# interface.net
KiCad netlist of a schematic drawn in Altium Designer
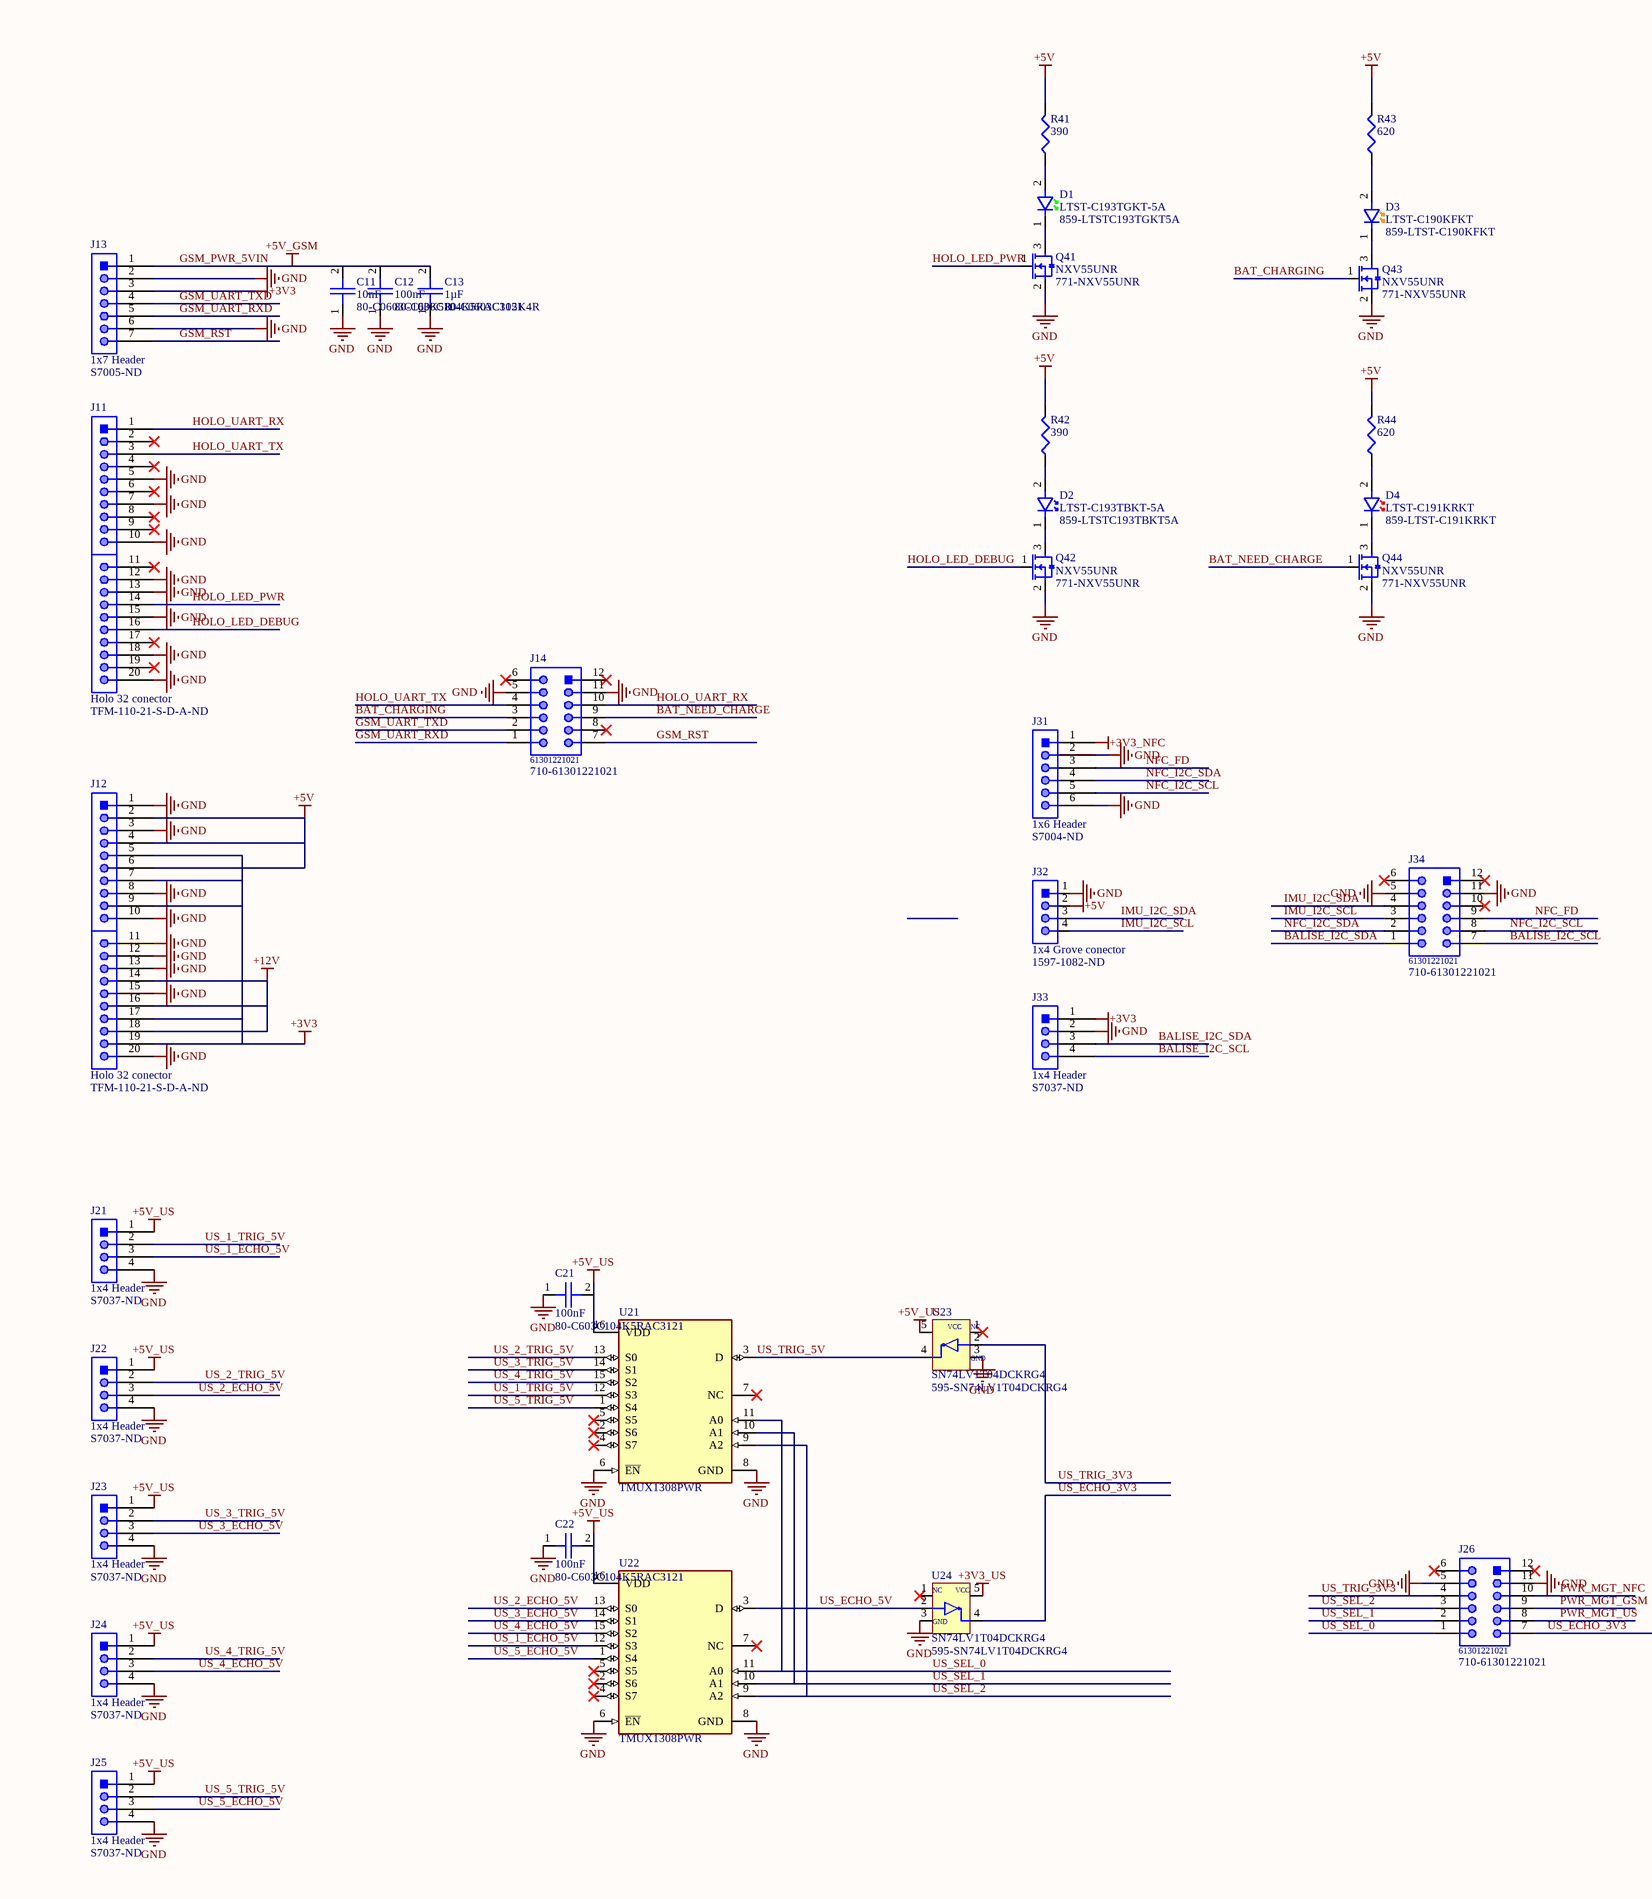
[diagram p0: interface.SchDoc, left]
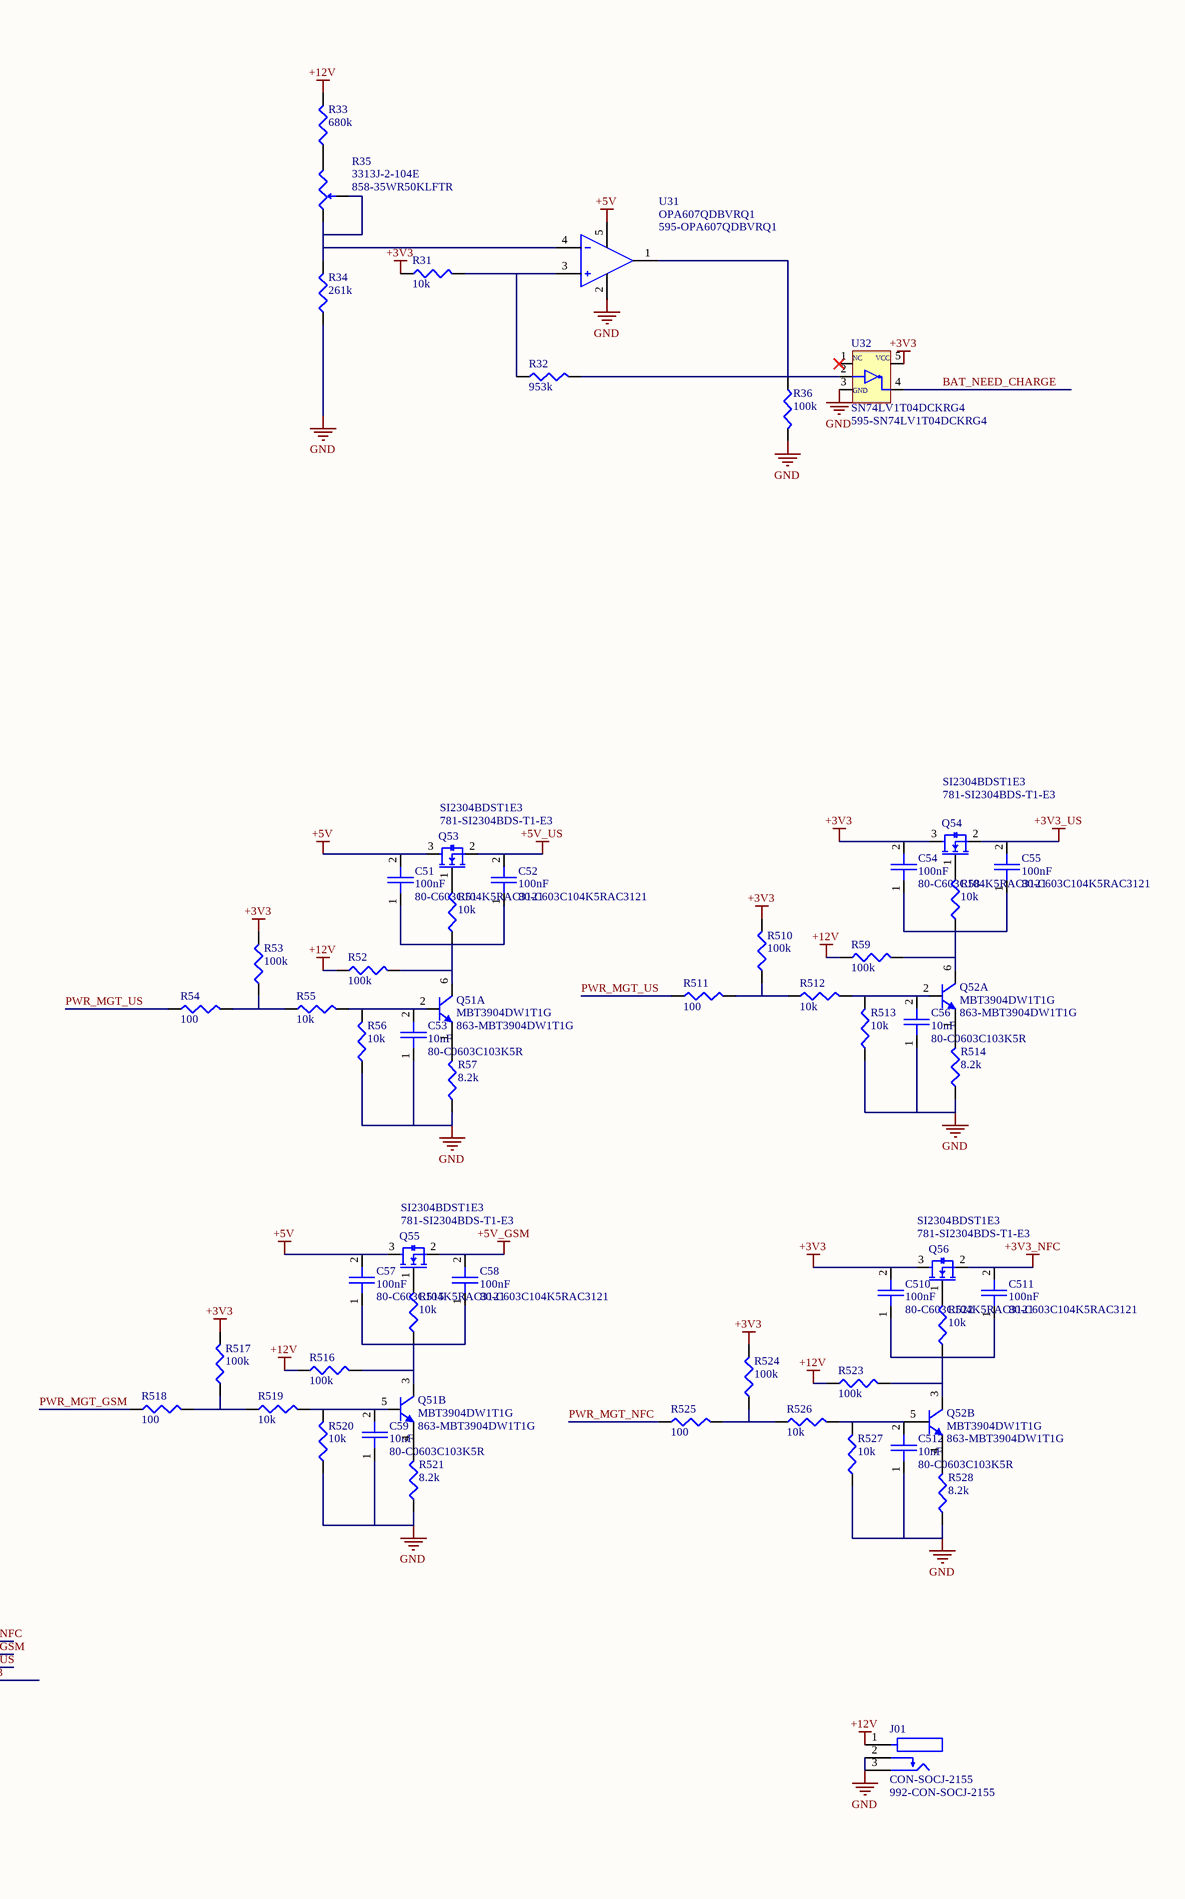
[diagram p1: interface.SchDoc, right]

(export (version "E")
  (design (tool "Eeschema 10.0.6"))
  (components
    (comp (ref "C11")
      (value "10nF")
      (footprint "FP-C0603C-CF-IPC_A")
      (description "CAP CER 10000PF 50V X7R 0603")
      (fields
        (field (name "MANUFACTURER") "KEMET")
        (field (name "MANUFACTURER PART NUMBER") "C0603C103K5RACTU")
        (field (name "SUPPLIER PART NUMBER 1") "80-C0603C103K5R")
      )
      (libsource (lib "interface_Schlib") (part "C0603C103K5RACTU"))
    )
    (comp (ref "C12")
      (value "100nF")
      (footprint "FP-C0603C104K5RAC3121-IPC_A")
      (description "Cap Ceramic 0.1uF 50V X7R 10% Pad SMD 0603 125°C T/R")
      (fields
        (field (name "MANUFACTURER") "KEMET")
        (field (name "MANUFACTURER PART NUMBER") "C0603C104K5RAC3121")
        (field (name "SUPPLIER PART NUMBER 1") "80-C603C104K5RAC3121")
      )
      (libsource (lib "interface_Schlib") (part "C0603C104K5RAC3121"))
    )
    (comp (ref "C13")
      (value "1µF")
      (footprint "CAPC1608X90X35NL15T15")
      (description "Cap Ceramic 1uF 16V X7R 10% SMD 0603 125°C Paper T/R")
      (fields
        (field (name "MANUFACTURER") "KEMET")
        (field (name "MANUFACTURER PART NUMBER") "C0603C105K4RACTU")
        (field (name "SUPPLIER PART NUMBER 1") "80-C0603C105K4R")
      )
      (libsource (lib "interface_Schlib") (part "C0603C105K4RACTU"))
    )
    (comp (ref "C21")
      (value "100nF")
      (footprint "FP-C0603C104K5RAC3121-IPC_A")
      (description "Cap Ceramic 0.1uF 50V X7R 10% Pad SMD 0603 125°C T/R")
      (fields
        (field (name "MANUFACTURER") "KEMET")
        (field (name "MANUFACTURER PART NUMBER") "C0603C104K5RAC3121")
        (field (name "SUPPLIER PART NUMBER 1") "80-C603C104K5RAC3121")
      )
      (libsource (lib "interface_Schlib") (part "C0603C104K5RAC3121"))
    )
    (comp (ref "C22")
      (value "100nF")
      (footprint "FP-C0603C104K5RAC3121-IPC_A")
      (description "Cap Ceramic 0.1uF 50V X7R 10% Pad SMD 0603 125°C T/R")
      (fields
        (field (name "MANUFACTURER") "KEMET")
        (field (name "MANUFACTURER PART NUMBER") "C0603C104K5RAC3121")
        (field (name "SUPPLIER PART NUMBER 1") "80-C603C104K5RAC3121")
      )
      (libsource (lib "interface_Schlib") (part "C0603C104K5RAC3121"))
    )
    (comp (ref "C51")
      (value "100nF")
      (footprint "FP-C0603C104K5RAC3121-IPC_A")
      (description "Cap Ceramic 0.1uF 50V X7R 10% Pad SMD 0603 125°C T/R")
      (fields
        (field (name "MANUFACTURER") "KEMET")
        (field (name "MANUFACTURER PART NUMBER") "C0603C104K5RAC3121")
        (field (name "SUPPLIER PART NUMBER 1") "80-C603C104K5RAC3121")
      )
      (libsource (lib "interface_Schlib") (part "C0603C104K5RAC3121"))
    )
    (comp (ref "C52")
      (value "100nF")
      (footprint "FP-C0603C104K5RAC3121-IPC_A")
      (description "Cap Ceramic 0.1uF 50V X7R 10% Pad SMD 0603 125°C T/R")
      (fields
        (field (name "MANUFACTURER") "KEMET")
        (field (name "MANUFACTURER PART NUMBER") "C0603C104K5RAC3121")
        (field (name "SUPPLIER PART NUMBER 1") "80-C603C104K5RAC3121")
      )
      (libsource (lib "interface_Schlib") (part "C0603C104K5RAC3121"))
    )
    (comp (ref "C53")
      (value "10nF")
      (footprint "FP-C0603C-CF-IPC_A")
      (description "CAP CER 10000PF 50V X7R 0603")
      (fields
        (field (name "MANUFACTURER") "KEMET")
        (field (name "MANUFACTURER PART NUMBER") "C0603C103K5RACTU")
        (field (name "SUPPLIER PART NUMBER 1") "80-C0603C103K5R")
      )
      (libsource (lib "interface_Schlib") (part "C0603C103K5RACTU"))
    )
    (comp (ref "C54")
      (value "100nF")
      (footprint "FP-C0603C104K5RAC3121-IPC_A")
      (description "Cap Ceramic 0.1uF 50V X7R 10% Pad SMD 0603 125°C T/R")
      (fields
        (field (name "MANUFACTURER") "KEMET")
        (field (name "MANUFACTURER PART NUMBER") "C0603C104K5RAC3121")
        (field (name "SUPPLIER PART NUMBER 1") "80-C603C104K5RAC3121")
      )
      (libsource (lib "interface_Schlib") (part "C0603C104K5RAC3121"))
    )
    (comp (ref "C55")
      (value "100nF")
      (footprint "FP-C0603C104K5RAC3121-IPC_A")
      (description "Cap Ceramic 0.1uF 50V X7R 10% Pad SMD 0603 125°C T/R")
      (fields
        (field (name "MANUFACTURER") "KEMET")
        (field (name "MANUFACTURER PART NUMBER") "C0603C104K5RAC3121")
        (field (name "SUPPLIER PART NUMBER 1") "80-C603C104K5RAC3121")
      )
      (libsource (lib "interface_Schlib") (part "C0603C104K5RAC3121"))
    )
    (comp (ref "C56")
      (value "10nF")
      (footprint "FP-C0603C-CF-IPC_A")
      (description "CAP CER 10000PF 50V X7R 0603")
      (fields
        (field (name "MANUFACTURER") "KEMET")
        (field (name "MANUFACTURER PART NUMBER") "C0603C103K5RACTU")
        (field (name "SUPPLIER PART NUMBER 1") "80-C0603C103K5R")
      )
      (libsource (lib "interface_Schlib") (part "C0603C103K5RACTU"))
    )
    (comp (ref "C57")
      (value "100nF")
      (footprint "FP-C0603C104K5RAC3121-IPC_A")
      (description "Cap Ceramic 0.1uF 50V X7R 10% Pad SMD 0603 125°C T/R")
      (fields
        (field (name "MANUFACTURER") "KEMET")
        (field (name "MANUFACTURER PART NUMBER") "C0603C104K5RAC3121")
        (field (name "SUPPLIER PART NUMBER 1") "80-C603C104K5RAC3121")
      )
      (libsource (lib "interface_Schlib") (part "C0603C104K5RAC3121"))
    )
    (comp (ref "C58")
      (value "100nF")
      (footprint "FP-C0603C104K5RAC3121-IPC_A")
      (description "Cap Ceramic 0.1uF 50V X7R 10% Pad SMD 0603 125°C T/R")
      (fields
        (field (name "MANUFACTURER") "KEMET")
        (field (name "MANUFACTURER PART NUMBER") "C0603C104K5RAC3121")
        (field (name "SUPPLIER PART NUMBER 1") "80-C603C104K5RAC3121")
      )
      (libsource (lib "interface_Schlib") (part "C0603C104K5RAC3121"))
    )
    (comp (ref "C59")
      (value "10nF")
      (footprint "FP-C0603C-CF-IPC_A")
      (description "CAP CER 10000PF 50V X7R 0603")
      (fields
        (field (name "MANUFACTURER") "KEMET")
        (field (name "MANUFACTURER PART NUMBER") "C0603C103K5RACTU")
        (field (name "SUPPLIER PART NUMBER 1") "80-C0603C103K5R")
      )
      (libsource (lib "interface_Schlib") (part "C0603C103K5RACTU"))
    )
    (comp (ref "C510")
      (value "100nF")
      (footprint "FP-C0603C104K5RAC3121-IPC_A")
      (description "Cap Ceramic 0.1uF 50V X7R 10% Pad SMD 0603 125°C T/R")
      (fields
        (field (name "MANUFACTURER") "KEMET")
        (field (name "MANUFACTURER PART NUMBER") "C0603C104K5RAC3121")
        (field (name "SUPPLIER PART NUMBER 1") "80-C603C104K5RAC3121")
      )
      (libsource (lib "interface_Schlib") (part "C0603C104K5RAC3121"))
    )
    (comp (ref "C511")
      (value "100nF")
      (footprint "FP-C0603C104K5RAC3121-IPC_A")
      (description "Cap Ceramic 0.1uF 50V X7R 10% Pad SMD 0603 125°C T/R")
      (fields
        (field (name "MANUFACTURER") "KEMET")
        (field (name "MANUFACTURER PART NUMBER") "C0603C104K5RAC3121")
        (field (name "SUPPLIER PART NUMBER 1") "80-C603C104K5RAC3121")
      )
      (libsource (lib "interface_Schlib") (part "C0603C104K5RAC3121"))
    )
    (comp (ref "C512")
      (value "10nF")
      (footprint "FP-C0603C-CF-IPC_A")
      (description "CAP CER 10000PF 50V X7R 0603")
      (fields
        (field (name "MANUFACTURER") "KEMET")
        (field (name "MANUFACTURER PART NUMBER") "C0603C103K5RACTU")
        (field (name "SUPPLIER PART NUMBER 1") "80-C0603C103K5R")
      )
      (libsource (lib "interface_Schlib") (part "C0603C103K5RACTU"))
    )
    (comp (ref "D1")
      (value "LTST-C193TGKT-5A")
      (footprint "FP-LTST-C193TGKT-5A")
      (description "0603(H=0.35mm) 绿色 λD=520nm~535nm VR=5V VF=2.5V~3.1V IF=5mA PD=76mW")
      (fields
        (field (name "MANUFACTURER") "Vishay Lite-On")
        (field (name "SUPPLIER PART NUMBER 1") "859-LTSTC193TGKT5A")
      )
      (libsource (lib "interface_Schlib") (part "LTST-C193TGKT-5A"))
    )
    (comp (ref "D2")
      (value "LTST-C193TBKT-5A")
      (footprint "FP-LTST-C193TBKT-5A-MFG")
      (description "0603(H=0.35mm) 蓝色 λD=465nm~475nm VR=5V VF=2.65V~3.05V IF=5mA PD=76mW")
      (fields
        (field (name "MANUFACTURER") "Vishay Lite-On")
        (field (name "SUPPLIER PART NUMBER 1") "859-LTSTC193TBKT5A")
      )
      (libsource (lib "interface_Schlib") (part "LTST-C193TBKT-5A"))
    )
    (comp (ref "D3")
      (value "LTST-C190KFKT")
      (footprint "FP-LTST-C190KFKT-MFG")
      (description "0603(H=0.9mm) 橙色 λD=605nm VR=5V VF=2.0V~2.4V IF=20mA PD=75mW")
      (fields
        (field (name "MANUFACTURER") "Vishay Lite-On")
        (field (name "SUPPLIER PART NUMBER 1") "859-LTST-C190KFKT")
      )
      (libsource (lib "interface_Schlib") (part "LTST-C190KFKT"))
    )
    (comp (ref "D4")
      (value "LTST-C191KRKT")
      (footprint "FP-LTST-C191KRKT")
      (description "0603(H=0.65mm) 红色 λD=631nm VR=5V VF=2.0V~2.4V IF=20mA PD=75mW")
      (fields
        (field (name "MANUFACTURER") "Vishay Lite-On")
        (field (name "VOLTAGE") "2V")
        (field (name "SUPPLIER PART NUMBER 1") "859-LTST-C191KRKT")
      )
      (libsource (lib "interface_Schlib") (part "LTST-C191KRKT"))
    )
    (comp (ref "J01")
      (value "CON-SOCJ-2155")
      (footprint "GRAVITECH_CON-SOCJ-2155")
      (description "DC Power Connectors Power Jack/Connector 2.1mm x 5.5mm")
      (fields
        (field (name "MANUFACTURER") "Gravitech")
        (field (name "SUPPLIER PART NUMBER 1") "992-CON-SOCJ-2155")
      )
      (libsource (lib "interface_Schlib") (part "CON-SOCJ-2155"))
    )
    (comp (ref "J11")
      (value "Holo 32 conector")
      (footprint "SAMTEC_TFM-110-21-S-D-A")
      (description "Headers & Wire Housings High-Reliability Tiger Eye Terminal Strips, .050 Pitch")
      (fields
        (field (name "MANUFACTURER") "Samtec")
        (field (name "MANUFACTURER PART NUMBER") "TFM-110-21-S-D-A")
        (field (name "SUPPLIER PART NUMBER 1") "TFM-110-21-S-D-A-ND")
      )
      (libsource (lib "interface_Schlib") (part "TFM-110-21-S-D-A"))
    )
    (comp (ref "J12")
      (value "Holo 32 conector")
      (footprint "SAMTEC_TFM-110-21-S-D-A")
      (description "Headers & Wire Housings High-Reliability Tiger Eye Terminal Strips, .050 Pitch")
      (fields
        (field (name "MANUFACTURER") "Samtec")
        (field (name "MANUFACTURER PART NUMBER") "TFM-110-21-S-D-A")
        (field (name "SUPPLIER PART NUMBER 1") "TFM-110-21-S-D-A-ND")
      )
      (libsource (lib "interface_Schlib") (part "TFM-110-21-S-D-A"))
    )
    (comp (ref "J13")
      (value "1x7 Header")
      (footprint "header 1x7")
      (description "Female, 7C, Straight, .100\"CC; 3.20mm Tail, No Mt. 100u\" Tin; PBT, Phos Bronze, 105 C")
      (fields
        (field (name "MANUFACTURER") "Sullins")
        (field (name "MANUFACTURER PART NUMBER") "PPTC071LFBN-RC")
        (field (name "SUPPLIER PART NUMBER 1") "S7005-ND")
      )
      (libsource (lib "interface_Schlib") (part "PPTC071LFBN-RC"))
    )
    (comp (ref "J14")
      (value "61301221021")
      (footprint "61301221021")
      (description "THT Angled Pin Header WR-PHD, Pitch 2.54 mm, Dual Row, 12 pins")
      (fields
        (field (name "MANUFACTURER") "Wurth Elektronik")
        (field (name "SUPPLIER PART NUMBER 1") "710-61301221021")
        (field (name "PUBLISHER") "WurthElektronik")
      )
      (libsource (lib "interface_Schlib") (part "61301221021"))
    )
    (comp (ref "J21")
      (value "1x4 Header")
      (footprint "header 1x4")
      (description "4 Positions Embase Connecteur 0,100 po (2,54mm) Trou traversant Or")
      (fields
        (field (name "MANUFACTURER") "Sullins")
        (field (name "MANUFACTURER PART NUMBER") "PPPC041LFBN-RC")
        (field (name "SUPPLIER PART NUMBER 1") "S7037-ND")
      )
      (libsource (lib "interface_Schlib") (part "PPPC041LFBN-RC"))
    )
    (comp (ref "J22")
      (value "1x4 Header")
      (footprint "header 1x4")
      (description "4 Positions Embase Connecteur 0,100 po (2,54mm) Trou traversant Or")
      (fields
        (field (name "MANUFACTURER") "Sullins")
        (field (name "MANUFACTURER PART NUMBER") "PPPC041LFBN-RC")
        (field (name "SUPPLIER PART NUMBER 1") "S7037-ND")
      )
      (libsource (lib "interface_Schlib") (part "PPPC041LFBN-RC"))
    )
    (comp (ref "J23")
      (value "1x4 Header")
      (footprint "header 1x4")
      (description "4 Positions Embase Connecteur 0,100 po (2,54mm) Trou traversant Or")
      (fields
        (field (name "MANUFACTURER") "Sullins")
        (field (name "MANUFACTURER PART NUMBER") "PPPC041LFBN-RC")
        (field (name "SUPPLIER PART NUMBER 1") "S7037-ND")
      )
      (libsource (lib "interface_Schlib") (part "PPPC041LFBN-RC"))
    )
    (comp (ref "J24")
      (value "1x4 Header")
      (footprint "header 1x4")
      (description "4 Positions Embase Connecteur 0,100 po (2,54mm) Trou traversant Or")
      (fields
        (field (name "MANUFACTURER") "Sullins")
        (field (name "MANUFACTURER PART NUMBER") "PPPC041LFBN-RC")
        (field (name "SUPPLIER PART NUMBER 1") "S7037-ND")
      )
      (libsource (lib "interface_Schlib") (part "PPPC041LFBN-RC"))
    )
    (comp (ref "J25")
      (value "1x4 Header")
      (footprint "header 1x4")
      (description "4 Positions Embase Connecteur 0,100 po (2,54mm) Trou traversant Or")
      (fields
        (field (name "MANUFACTURER") "Sullins")
        (field (name "MANUFACTURER PART NUMBER") "PPPC041LFBN-RC")
        (field (name "SUPPLIER PART NUMBER 1") "S7037-ND")
      )
      (libsource (lib "interface_Schlib") (part "PPPC041LFBN-RC"))
    )
    (comp (ref "J26")
      (value "61301221021")
      (footprint "61301221021")
      (description "THT Angled Pin Header WR-PHD, Pitch 2.54 mm, Dual Row, 12 pins")
      (fields
        (field (name "MANUFACTURER") "Wurth Elektronik")
        (field (name "SUPPLIER PART NUMBER 1") "710-61301221021")
        (field (name "PUBLISHER") "WurthElektronik")
      )
      (libsource (lib "interface_Schlib") (part "61301221021"))
    )
    (comp (ref "J31")
      (value "1x6 Header")
      (footprint "header 1x6")
      (description "Female, 6 C, Straight, .100\"CC; 3.20mm Tail, No Mt. 100u\" Tin; PBT, Phos Bronze, 105 C")
      (fields
        (field (name "MANUFACTURER") "Sullins")
        (field (name "MANUFACTURER PART NUMBER") "PPTC061LFBN-RC")
        (field (name "SUPPLIER PART NUMBER 1") "S7004-ND")
      )
      (libsource (lib "interface_Schlib") (part "PPTC061LFBN-RC"))
    )
    (comp (ref "J32")
      (value "1x4 Grove conector")
      (footprint "FP-110990030")
      (description "Grove - Universal 4 pin connector [Seeed Studio] 110990030 Grove - Universal 4 pin connector")
      (fields
        (field (name "MANUFACTURER") "Seeed Studio")
        (field (name "MANUFACTURER PART NUMBER") "110990030")
        (field (name "SUPPLIER PART NUMBER 1") "1597-1082-ND")
      )
      (libsource (lib "interface_Schlib") (part "110990030"))
    )
    (comp (ref "J33")
      (value "1x4 Header")
      (footprint "header 1x4")
      (description "4 Positions Embase Connecteur 0,100 po (2,54mm) Trou traversant Or")
      (fields
        (field (name "MANUFACTURER") "Sullins")
        (field (name "MANUFACTURER PART NUMBER") "PPPC041LFBN-RC")
        (field (name "SUPPLIER PART NUMBER 1") "S7037-ND")
      )
      (libsource (lib "interface_Schlib") (part "PPPC041LFBN-RC"))
    )
    (comp (ref "J34")
      (value "61301221021")
      (footprint "61301221021")
      (description "THT Angled Pin Header WR-PHD, Pitch 2.54 mm, Dual Row, 12 pins")
      (fields
        (field (name "MANUFACTURER") "Wurth Elektronik")
        (field (name "SUPPLIER PART NUMBER 1") "710-61301221021")
        (field (name "PUBLISHER") "WurthElektronik")
      )
      (libsource (lib "interface_Schlib") (part "61301221021"))
    )
    (comp (ref "Q41")
      (value "NXV55UNR")
      (footprint "SOT95P230X110-3N")
      (description "Transistor MOSFET N-Channel 30V 2.3A 3-Pin SOT-23")
      (fields (field (name "MANUFACTURER") "Nexperia") (field (name "SUPPLIER PART NUMBER 1") "771-NXV55UNR"))
      (libsource (lib "interface_Schlib") (part "NXV55UNR"))
    )
    (comp (ref "Q42")
      (value "NXV55UNR")
      (footprint "SOT95P230X110-3N")
      (description "Transistor MOSFET N-Channel 30V 2.3A 3-Pin SOT-23")
      (fields (field (name "MANUFACTURER") "Nexperia") (field (name "SUPPLIER PART NUMBER 1") "771-NXV55UNR"))
      (libsource (lib "interface_Schlib") (part "NXV55UNR"))
    )
    (comp (ref "Q43")
      (value "NXV55UNR")
      (footprint "SOT95P230X110-3N")
      (description "Transistor MOSFET N-Channel 30V 2.3A 3-Pin SOT-23")
      (fields (field (name "MANUFACTURER") "Nexperia") (field (name "SUPPLIER PART NUMBER 1") "771-NXV55UNR"))
      (libsource (lib "interface_Schlib") (part "NXV55UNR"))
    )
    (comp (ref "Q44")
      (value "NXV55UNR")
      (footprint "SOT95P230X110-3N")
      (description "Transistor MOSFET N-Channel 30V 2.3A 3-Pin SOT-23")
      (fields (field (name "MANUFACTURER") "Nexperia") (field (name "SUPPLIER PART NUMBER 1") "771-NXV55UNR"))
      (libsource (lib "interface_Schlib") (part "NXV55UNR"))
    )
    (comp (ref "Q51")
      (value "MBT3904DW1T1G")
      (footprint "ONSC-SOT-363-6-419B-02_W_V")
      (description "Dual General Purpose Transistors, 6-Pin SOT-363, Pb-Free, Tape and Reel")
      (fields
        (field (name "MANUFACTURER") "On Semiconductor")
        (field (name "SUPPLIER PART NUMBER 1") "863-MBT3904DW1T1G")
      )
      (libsource (lib "interface_Schlib") (part "CMP-1048-00877-1"))
    )
    (comp (ref "Q52")
      (value "MBT3904DW1T1G")
      (footprint "ONSC-SOT-363-6-419B-02_W_V")
      (description "Dual General Purpose Transistors, 6-Pin SOT-363, Pb-Free, Tape and Reel")
      (fields
        (field (name "MANUFACTURER") "On Semiconductor")
        (field (name "SUPPLIER PART NUMBER 1") "863-MBT3904DW1T1G")
      )
      (libsource (lib "interface_Schlib") (part "CMP-1048-00877-1"))
    )
    (comp (ref "Q53")
      (value "SI2304BDST1E3")
      (footprint "FP-SI2304BDST1E3")
      (description "Single N-Channel 30 V 0.07 Ohms Surface Mount Power Mosfet - SOT-23")
      (fields
        (field (name "MANUFACTURER") "Vishay")
        (field (name "SUPPLIER PART NUMBER 1") "781-SI2304BDS-T1-E3")
      )
      (libsource (lib "interface_Schlib") (part "SI2304BDST1E3"))
    )
    (comp (ref "Q54")
      (value "SI2304BDST1E3")
      (footprint "FP-SI2304BDST1E3")
      (description "Single N-Channel 30 V 0.07 Ohms Surface Mount Power Mosfet - SOT-23")
      (fields
        (field (name "MANUFACTURER") "Vishay")
        (field (name "SUPPLIER PART NUMBER 1") "781-SI2304BDS-T1-E3")
      )
      (libsource (lib "interface_Schlib") (part "SI2304BDST1E3"))
    )
    (comp (ref "Q55")
      (value "SI2304BDST1E3")
      (footprint "FP-SI2304BDST1E3")
      (description "Single N-Channel 30 V 0.07 Ohms Surface Mount Power Mosfet - SOT-23")
      (fields
        (field (name "MANUFACTURER") "Vishay")
        (field (name "SUPPLIER PART NUMBER 1") "781-SI2304BDS-T1-E3")
      )
      (libsource (lib "interface_Schlib") (part "SI2304BDST1E3"))
    )
    (comp (ref "Q56")
      (value "SI2304BDST1E3")
      (footprint "FP-SI2304BDST1E3")
      (description "Single N-Channel 30 V 0.07 Ohms Surface Mount Power Mosfet - SOT-23")
      (fields
        (field (name "MANUFACTURER") "Vishay")
        (field (name "SUPPLIER PART NUMBER 1") "781-SI2304BDS-T1-E3")
      )
      (libsource (lib "interface_Schlib") (part "SI2304BDST1E3"))
    )
    (comp (ref "R31")
      (value "10k")
      (footprint "RESC2013X50X30ML20T20")
      (libsource (lib "interface_Schlib") (part "resistor"))
    )
    (comp (ref "R32")
      (value "953k")
      (footprint "RESC2013X50X30ML20T20")
      (libsource (lib "interface_Schlib") (part "resistor"))
    )
    (comp (ref "R33")
      (value "680k")
      (footprint "RESC2013X50X30ML20T20")
      (libsource (lib "interface_Schlib") (part "resistor"))
    )
    (comp (ref "R34")
      (value "261k")
      (footprint "RESC2013X50X30ML20T20")
      (libsource (lib "interface_Schlib") (part "resistor"))
    )
    (comp (ref "R35")
      (value "3313J-2-104E")
      (footprint "FP-3313J-2-104E")
      (description "35W Series 3 mm Open Frame 50 kOhm ±25 % Single-Turn Trimming Potentiometer")
      (fields
        (field (name "MANUFACTURER") "TT BI")
        (field (name "MANUFACTURER PART NUMBER") "35WR50KLFTR")
        (field (name "SUPPLIER PART NUMBER 1") "858-35WR50KLFTR")
      )
      (libsource (lib "interface_Schlib") (part "35WR50KLFTR"))
    )
    (comp (ref "R36")
      (value "100k")
      (footprint "RESC2013X50X30ML20T20")
      (libsource (lib "interface_Schlib") (part "resistor"))
    )
    (comp (ref "R41")
      (value "390")
      (footprint "RESC2013X50X30ML20T20")
      (libsource (lib "interface_Schlib") (part "resistor"))
    )
    (comp (ref "R42")
      (value "390")
      (footprint "RESC2013X50X30ML20T20")
      (libsource (lib "interface_Schlib") (part "resistor"))
    )
    (comp (ref "R43")
      (value "620")
      (footprint "RESC2013X50X30ML20T20")
      (libsource (lib "interface_Schlib") (part "resistor"))
    )
    (comp (ref "R44")
      (value "620")
      (footprint "RESC2013X50X30ML20T20")
      (libsource (lib "interface_Schlib") (part "resistor"))
    )
    (comp (ref "R51")
      (value "10k")
      (footprint "RESC2013X50X30ML20T20")
      (libsource (lib "interface_Schlib") (part "resistor"))
    )
    (comp (ref "R52")
      (value "100k")
      (footprint "RESC2013X50X30ML20T20")
      (libsource (lib "interface_Schlib") (part "resistor"))
    )
    (comp (ref "R53")
      (value "100k")
      (footprint "RESC2013X50X30ML20T20")
      (libsource (lib "interface_Schlib") (part "resistor"))
    )
    (comp (ref "R54")
      (value "100")
      (footprint "RESC2013X50X30ML20T20")
      (libsource (lib "interface_Schlib") (part "resistor"))
    )
    (comp (ref "R55")
      (value "10k")
      (footprint "RESC2013X50X30ML20T20")
      (libsource (lib "interface_Schlib") (part "resistor"))
    )
    (comp (ref "R56")
      (value "10k")
      (footprint "RESC2013X50X30ML20T20")
      (libsource (lib "interface_Schlib") (part "resistor"))
    )
    (comp (ref "R57")
      (value "8.2k")
      (footprint "RESC2013X50X30ML20T20")
      (libsource (lib "interface_Schlib") (part "resistor"))
    )
    (comp (ref "R58")
      (value "10k")
      (footprint "RESC2013X50X30ML20T20")
      (libsource (lib "interface_Schlib") (part "resistor"))
    )
    (comp (ref "R59")
      (value "100k")
      (footprint "RESC2013X50X30ML20T20")
      (libsource (lib "interface_Schlib") (part "resistor"))
    )
    (comp (ref "R510")
      (value "100k")
      (footprint "RESC2013X50X30ML20T20")
      (libsource (lib "interface_Schlib") (part "resistor"))
    )
    (comp (ref "R511")
      (value "100")
      (footprint "RESC2013X50X30ML20T20")
      (libsource (lib "interface_Schlib") (part "resistor"))
    )
    (comp (ref "R512")
      (value "10k")
      (footprint "RESC2013X50X30ML20T20")
      (libsource (lib "interface_Schlib") (part "resistor"))
    )
    (comp (ref "R513")
      (value "10k")
      (footprint "RESC2013X50X30ML20T20")
      (libsource (lib "interface_Schlib") (part "resistor"))
    )
    (comp (ref "R514")
      (value "8.2k")
      (footprint "RESC2013X50X30ML20T20")
      (libsource (lib "interface_Schlib") (part "resistor"))
    )
    (comp (ref "R515")
      (value "10k")
      (footprint "RESC2013X50X30ML20T20")
      (libsource (lib "interface_Schlib") (part "resistor"))
    )
    (comp (ref "R516")
      (value "100k")
      (footprint "RESC2013X50X30ML20T20")
      (libsource (lib "interface_Schlib") (part "resistor"))
    )
    (comp (ref "R517")
      (value "100k")
      (footprint "RESC2013X50X30ML20T20")
      (libsource (lib "interface_Schlib") (part "resistor"))
    )
    (comp (ref "R518")
      (value "100")
      (footprint "RESC2013X50X30ML20T20")
      (libsource (lib "interface_Schlib") (part "resistor"))
    )
    (comp (ref "R519")
      (value "10k")
      (footprint "RESC2013X50X30ML20T20")
      (libsource (lib "interface_Schlib") (part "resistor"))
    )
    (comp (ref "R520")
      (value "10k")
      (footprint "RESC2013X50X30ML20T20")
      (libsource (lib "interface_Schlib") (part "resistor"))
    )
    (comp (ref "R521")
      (value "8.2k")
      (footprint "RESC2013X50X30ML20T20")
      (libsource (lib "interface_Schlib") (part "resistor"))
    )
    (comp (ref "R522")
      (value "10k")
      (footprint "RESC2013X50X30ML20T20")
      (libsource (lib "interface_Schlib") (part "resistor"))
    )
    (comp (ref "R523")
      (value "100k")
      (footprint "RESC2013X50X30ML20T20")
      (libsource (lib "interface_Schlib") (part "resistor"))
    )
    (comp (ref "R524")
      (value "100k")
      (footprint "RESC2013X50X30ML20T20")
      (libsource (lib "interface_Schlib") (part "resistor"))
    )
    (comp (ref "R525")
      (value "100")
      (footprint "RESC2013X50X30ML20T20")
      (libsource (lib "interface_Schlib") (part "resistor"))
    )
    (comp (ref "R526")
      (value "10k")
      (footprint "RESC2013X50X30ML20T20")
      (libsource (lib "interface_Schlib") (part "resistor"))
    )
    (comp (ref "R527")
      (value "10k")
      (footprint "RESC2013X50X30ML20T20")
      (libsource (lib "interface_Schlib") (part "resistor"))
    )
    (comp (ref "R528")
      (value "8.2k")
      (footprint "RESC2013X50X30ML20T20")
      (libsource (lib "interface_Schlib") (part "resistor"))
    )
    (comp (ref "U21")
      (value "TMUX1308PWR")
      (footprint "FP-PW0016A-IPC_A")
      (description "1-CHANNEL, 8:1 GENERAL-PURPOSE A")
      (libsource (lib "interface_Schlib") (part "CMP-04892-000071-1"))
    )
    (comp (ref "U22")
      (value "TMUX1308PWR")
      (footprint "FP-PW0016A-IPC_A")
      (description "1-CHANNEL, 8:1 GENERAL-PURPOSE A")
      (libsource (lib "interface_Schlib") (part "CMP-04892-000071-1"))
    )
    (comp (ref "U23")
      (value "SN74LV1T04DCKRG4")
      (footprint "SOT65P210X110-5N")
      (description "Single Power Supply INVERTER Gate logic level shifter 5-SC70")
      (fields
        (field (name "MANUFACTURER") "Texas Instruments")
        (field (name "SUPPLIER PART NUMBER 1") "595-SN74LV1T04DCKRG4")
      )
      (libsource (lib "") (part "SN74LV1T04DCKRG4_1"))
    )
    (comp (ref "U24")
      (value "SN74LV1T04DCKRG4")
      (footprint "SOT65P210X110-5N")
      (description "Single Power Supply INVERTER Gate logic level shifter 5-SC70")
      (fields
        (field (name "MANUFACTURER") "Texas Instruments")
        (field (name "SUPPLIER PART NUMBER 1") "595-SN74LV1T04DCKRG4")
      )
      (libsource (lib "interface_Schlib") (part "SN74LV1T04DCKRG4"))
    )
    (comp (ref "U31")
      (value "OPA607QDBVRQ1")
      (footprint "FP-DBV0005A-IPC_A")
      (fields
        (field (name "MANUFACTURER") "Texas Instruments")
        (field (name "SUPPLIER PART NUMBER 1") "595-OPA607QDBVRQ1")
      )
      (libsource (lib "interface_Schlib") (part "OPA607QDBVRQ1"))
    )
    (comp (ref "U32")
      (value "SN74LV1T04DCKRG4")
      (footprint "SOT65P210X110-5N")
      (description "Single Power Supply INVERTER Gate logic level shifter 5-SC70")
      (fields
        (field (name "MANUFACTURER") "Texas Instruments")
        (field (name "SUPPLIER PART NUMBER 1") "595-SN74LV1T04DCKRG4")
      )
      (libsource (lib "interface_Schlib") (part "SN74LV1T04DCKRG4"))
    )
  )
  (nets
    (net (code "1") (name "+3V3") (class "Default")
      (node (ref "C510") (pin "2") (pinfunction "2_2") (pintype "passive"))
      (node (ref "C54") (pin "2") (pinfunction "2_2") (pintype "passive"))
      (node (ref "J12") (pin "17") (pinfunction "17_17") (pintype "passive"))
      (node (ref "J12") (pin "19") (pinfunction "19_19") (pintype "passive"))
      (node (ref "J12") (pin "5") (pinfunction "5_5") (pintype "passive"))
      (node (ref "J12") (pin "7") (pinfunction "7_7") (pintype "passive"))
      (node (ref "J12") (pin "9") (pinfunction "9_9") (pintype "passive"))
      (node (ref "J13") (pin "3") (pinfunction "3_3") (pintype "passive"))
      (node (ref "J33") (pin "1") (pinfunction "1_1") (pintype "passive"))
      (node (ref "Q54") (pin "3") (pinfunction "3_3") (pintype "passive"))
      (node (ref "Q56") (pin "3") (pinfunction "3_3") (pintype "passive"))
      (node (ref "R31") (pin "1") (pinfunction "1_1") (pintype "passive"))
      (node (ref "R510") (pin "2") (pinfunction "2_2") (pintype "passive"))
      (node (ref "R517") (pin "2") (pinfunction "2_2") (pintype "passive"))
      (node (ref "R524") (pin "2") (pinfunction "2_2") (pintype "passive"))
      (node (ref "R53") (pin "2") (pinfunction "2_2") (pintype "passive"))
      (node (ref "U32") (pin "5") (pinfunction "VCC_5") (pintype "passive"))
    )
    (net (code "2") (name "+3V3_NFC") (class "Default")
      (node (ref "C511") (pin "2") (pinfunction "2_2") (pintype "passive"))
      (node (ref "J31") (pin "1") (pinfunction "1_1") (pintype "passive"))
      (node (ref "Q56") (pin "2") (pinfunction "2_2") (pintype "passive"))
    )
    (net (code "3") (name "+3V3_US") (class "Default")
      (node (ref "C55") (pin "2") (pinfunction "2_2") (pintype "passive"))
      (node (ref "Q54") (pin "2") (pinfunction "2_2") (pintype "passive"))
      (node (ref "U24") (pin "5") (pinfunction "VCC_5") (pintype "passive"))
    )
    (net (code "4") (name "+5V") (class "Default")
      (node (ref "C51") (pin "2") (pinfunction "2_2") (pintype "passive"))
      (node (ref "C57") (pin "2") (pinfunction "2_2") (pintype "passive"))
      (node (ref "J12") (pin "2") (pinfunction "2_2") (pintype "passive"))
      (node (ref "J12") (pin "4") (pinfunction "4_4") (pintype "passive"))
      (node (ref "J12") (pin "6") (pinfunction "6_6") (pintype "passive"))
      (node (ref "J32") (pin "2") (pinfunction "2_2") (pintype "passive"))
      (node (ref "Q53") (pin "3") (pinfunction "3_3") (pintype "passive"))
      (node (ref "Q55") (pin "3") (pinfunction "3_3") (pintype "passive"))
      (node (ref "R41") (pin "2") (pinfunction "2_2") (pintype "passive"))
      (node (ref "R42") (pin "2") (pinfunction "2_2") (pintype "passive"))
      (node (ref "R43") (pin "2") (pinfunction "2_2") (pintype "passive"))
      (node (ref "R44") (pin "2") (pinfunction "2_2") (pintype "passive"))
      (node (ref "U31") (pin "5") (pinfunction "VS+_5") (pintype "power_in"))
    )
    (net (code "5") (name "+5V_GSM") (class "Default")
      (node (ref "C11") (pin "2") (pinfunction "2_2") (pintype "passive"))
      (node (ref "C12") (pin "2") (pinfunction "2_2") (pintype "passive"))
      (node (ref "C13") (pin "2") (pinfunction "2_2") (pintype "passive"))
      (node (ref "C58") (pin "2") (pinfunction "2_2") (pintype "passive"))
      (node (ref "J13") (pin "1") (pinfunction "1_1") (pintype "passive"))
      (node (ref "Q55") (pin "2") (pinfunction "2_2") (pintype "passive"))
    )
    (net (code "6") (name "+5V_US") (class "Default")
      (node (ref "C21") (pin "2") (pinfunction "2_2") (pintype "passive"))
      (node (ref "C22") (pin "2") (pinfunction "2_2") (pintype "passive"))
      (node (ref "C52") (pin "2") (pinfunction "2_2") (pintype "passive"))
      (node (ref "J21") (pin "1") (pinfunction "1_1") (pintype "passive"))
      (node (ref "J22") (pin "1") (pinfunction "1_1") (pintype "passive"))
      (node (ref "J23") (pin "1") (pinfunction "1_1") (pintype "passive"))
      (node (ref "J24") (pin "1") (pinfunction "1_1") (pintype "passive"))
      (node (ref "J25") (pin "1") (pinfunction "1_1") (pintype "passive"))
      (node (ref "Q53") (pin "2") (pinfunction "2_2") (pintype "passive"))
      (node (ref "U21") (pin "16") (pinfunction "VDD_16") (pintype "power_in"))
      (node (ref "U22") (pin "16") (pinfunction "VDD_16") (pintype "power_in"))
      (node (ref "U23") (pin "5") (pinfunction "VCC_5") (pintype "passive"))
    )
    (net (code "7") (name "+12V") (class "Default")
      (node (ref "J01") (pin "1") (pinfunction "1_1") (pintype "passive"))
      (node (ref "J12") (pin "14") (pinfunction "14_14") (pintype "passive"))
      (node (ref "J12") (pin "16") (pinfunction "16_16") (pintype "passive"))
      (node (ref "J12") (pin "18") (pinfunction "18_18") (pintype "passive"))
      (node (ref "R33") (pin "2") (pinfunction "2_2") (pintype "passive"))
      (node (ref "R516") (pin "1") (pinfunction "1_1") (pintype "passive"))
      (node (ref "R52") (pin "1") (pinfunction "1_1") (pintype "passive"))
      (node (ref "R523") (pin "1") (pinfunction "1_1") (pintype "passive"))
      (node (ref "R59") (pin "1") (pinfunction "1_1") (pintype "passive"))
    )
    (net (code "8") (name "/BALISE_I2C_SCL") (class "Default")
      (node (ref "J33") (pin "4") (pinfunction "4_4") (pintype "passive"))
      (node (ref "J34") (pin "7") (pinfunction "7_7") (pintype "passive"))
    )
    (net (code "9") (name "/BALISE_I2C_SDA") (class "Default")
      (node (ref "J33") (pin "3") (pinfunction "3_3") (pintype "passive"))
      (node (ref "J34") (pin "1") (pinfunction "1_1") (pintype "passive"))
    )
    (net (code "10") (name "/BAT_CHARGING") (class "Default")
      (node (ref "J14") (pin "3") (pinfunction "3_3") (pintype "passive"))
      (node (ref "Q43") (pin "1") (pinfunction "1_1") (pintype "passive"))
    )
    (net (code "11") (name "/BAT_NEED_CHARGE") (class "Default")
      (node (ref "J14") (pin "9") (pinfunction "9_9") (pintype "passive"))
      (node (ref "Q44") (pin "1") (pinfunction "1_1") (pintype "passive"))
      (node (ref "U32") (pin "4") (pinfunction "4_4") (pintype "passive"))
    )
    (net (code "12") (name "/GSM_RST") (class "Default")
      (node (ref "J13") (pin "7") (pinfunction "7_7") (pintype "passive"))
      (node (ref "J14") (pin "7") (pinfunction "7_7") (pintype "passive"))
    )
    (net (code "13") (name "/GSM_UART_RXD") (class "Default")
      (node (ref "J13") (pin "5") (pinfunction "5_5") (pintype "passive"))
      (node (ref "J14") (pin "1") (pinfunction "1_1") (pintype "passive"))
    )
    (net (code "14") (name "/GSM_UART_TXD") (class "Default")
      (node (ref "J13") (pin "4") (pinfunction "4_4") (pintype "passive"))
      (node (ref "J14") (pin "2") (pinfunction "2_2") (pintype "passive"))
    )
    (net (code "15") (name "/HOLO_LED_DEBUG") (class "Default")
      (node (ref "J11") (pin "16") (pinfunction "16_16") (pintype "passive"))
      (node (ref "Q42") (pin "1") (pinfunction "1_1") (pintype "passive"))
    )
    (net (code "16") (name "/HOLO_LED_PWR") (class "Default")
      (node (ref "J11") (pin "14") (pinfunction "14_14") (pintype "passive"))
      (node (ref "Q41") (pin "1") (pinfunction "1_1") (pintype "passive"))
    )
    (net (code "17") (name "/HOLO_UART_RX") (class "Default")
      (node (ref "J11") (pin "1") (pinfunction "1_1") (pintype "passive"))
      (node (ref "J14") (pin "10") (pinfunction "10_10") (pintype "passive"))
    )
    (net (code "18") (name "/HOLO_UART_TX") (class "Default")
      (node (ref "J11") (pin "3") (pinfunction "3_3") (pintype "passive"))
      (node (ref "J14") (pin "4") (pinfunction "4_4") (pintype "passive"))
    )
    (net (code "19") (name "/IMU_I2C_SCL") (class "Default")
      (node (ref "J32") (pin "4") (pinfunction "4_4") (pintype "passive"))
      (node (ref "J34") (pin "3") (pinfunction "3_3") (pintype "passive"))
    )
    (net (code "20") (name "/IMU_I2C_SDA") (class "Default")
      (node (ref "J32") (pin "3") (pinfunction "3_3") (pintype "passive"))
      (node (ref "J34") (pin "4") (pinfunction "4_4") (pintype "passive"))
    )
    (net (code "21") (name "/NFC_FD") (class "Default")
      (node (ref "J31") (pin "3") (pinfunction "3_3") (pintype "passive"))
      (node (ref "J34") (pin "9") (pinfunction "9_9") (pintype "passive"))
    )
    (net (code "22") (name "/NFC_I2C_SCL") (class "Default")
      (node (ref "J31") (pin "5") (pinfunction "5_5") (pintype "passive"))
      (node (ref "J34") (pin "8") (pinfunction "8_8") (pintype "passive"))
    )
    (net (code "23") (name "/NFC_I2C_SDA") (class "Default")
      (node (ref "J31") (pin "4") (pinfunction "4_4") (pintype "passive"))
      (node (ref "J34") (pin "2") (pinfunction "2_2") (pintype "passive"))
    )
    (net (code "24") (name "/PWR_MGT_GSM") (class "Default")
      (node (ref "J26") (pin "9") (pinfunction "9_9") (pintype "passive"))
      (node (ref "R518") (pin "1") (pinfunction "1_1") (pintype "passive"))
    )
    (net (code "25") (name "/PWR_MGT_NFC") (class "Default")
      (node (ref "J26") (pin "10") (pinfunction "10_10") (pintype "passive"))
      (node (ref "R525") (pin "1") (pinfunction "1_1") (pintype "passive"))
    )
    (net (code "26") (name "/PWR_MGT_US") (class "Default")
      (node (ref "J26") (pin "8") (pinfunction "8_8") (pintype "passive"))
      (node (ref "R511") (pin "1") (pinfunction "1_1") (pintype "passive"))
      (node (ref "R54") (pin "1") (pinfunction "1_1") (pintype "passive"))
    )
    (net (code "27") (name "/US_1_ECHO_5V") (class "Default")
      (node (ref "J21") (pin "3") (pinfunction "3_3") (pintype "passive"))
      (node (ref "U22") (pin "12") (pinfunction "S3_12") (pintype "bidirectional"))
    )
    (net (code "28") (name "/US_1_TRIG_5V") (class "Default")
      (node (ref "J21") (pin "2") (pinfunction "2_2") (pintype "passive"))
      (node (ref "U21") (pin "12") (pinfunction "S3_12") (pintype "bidirectional"))
    )
    (net (code "29") (name "/US_2_ECHO_5V") (class "Default")
      (node (ref "J22") (pin "3") (pinfunction "3_3") (pintype "passive"))
      (node (ref "U22") (pin "13") (pinfunction "S0_13") (pintype "bidirectional"))
    )
    (net (code "30") (name "/US_2_TRIG_5V") (class "Default")
      (node (ref "J22") (pin "2") (pinfunction "2_2") (pintype "passive"))
      (node (ref "U21") (pin "13") (pinfunction "S0_13") (pintype "bidirectional"))
    )
    (net (code "31") (name "/US_3_ECHO_5V") (class "Default")
      (node (ref "J23") (pin "3") (pinfunction "3_3") (pintype "passive"))
      (node (ref "U22") (pin "14") (pinfunction "S1_14") (pintype "bidirectional"))
    )
    (net (code "32") (name "/US_3_TRIG_5V") (class "Default")
      (node (ref "J23") (pin "2") (pinfunction "2_2") (pintype "passive"))
      (node (ref "U21") (pin "14") (pinfunction "S1_14") (pintype "bidirectional"))
    )
    (net (code "33") (name "/US_4_ECHO_5V") (class "Default")
      (node (ref "J24") (pin "3") (pinfunction "3_3") (pintype "passive"))
      (node (ref "U22") (pin "15") (pinfunction "S2_15") (pintype "bidirectional"))
    )
    (net (code "34") (name "/US_4_TRIG_5V") (class "Default")
      (node (ref "J24") (pin "2") (pinfunction "2_2") (pintype "passive"))
      (node (ref "U21") (pin "15") (pinfunction "S2_15") (pintype "bidirectional"))
    )
    (net (code "35") (name "/US_5_ECHO_5V") (class "Default")
      (node (ref "J25") (pin "3") (pinfunction "3_3") (pintype "passive"))
      (node (ref "U22") (pin "1") (pinfunction "S4_1") (pintype "bidirectional"))
    )
    (net (code "36") (name "/US_5_TRIG_5V") (class "Default")
      (node (ref "J25") (pin "2") (pinfunction "2_2") (pintype "passive"))
      (node (ref "U21") (pin "1") (pinfunction "S4_1") (pintype "bidirectional"))
    )
    (net (code "37") (name "/US_ECHO_3V3") (class "Default")
      (node (ref "J26") (pin "7") (pinfunction "7_7") (pintype "passive"))
      (node (ref "U24") (pin "4") (pinfunction "4_4") (pintype "passive"))
    )
    (net (code "38") (name "/US_ECHO_5V") (class "Default")
      (node (ref "U22") (pin "3") (pinfunction "D_3") (pintype "bidirectional"))
      (node (ref "U24") (pin "2") (pinfunction "2_2") (pintype "passive"))
    )
    (net (code "39") (name "/US_SEL_0") (class "Default")
      (node (ref "J26") (pin "1") (pinfunction "1_1") (pintype "passive"))
      (node (ref "U21") (pin "11") (pinfunction "A0_11") (pintype "input"))
      (node (ref "U22") (pin "11") (pinfunction "A0_11") (pintype "input"))
    )
    (net (code "40") (name "/US_SEL_1") (class "Default")
      (node (ref "J26") (pin "2") (pinfunction "2_2") (pintype "passive"))
      (node (ref "U21") (pin "10") (pinfunction "A1_10") (pintype "input"))
      (node (ref "U22") (pin "10") (pinfunction "A1_10") (pintype "input"))
    )
    (net (code "41") (name "/US_SEL_2") (class "Default")
      (node (ref "J26") (pin "3") (pinfunction "3_3") (pintype "passive"))
      (node (ref "U21") (pin "9") (pinfunction "A2_9") (pintype "input"))
      (node (ref "U22") (pin "9") (pinfunction "A2_9") (pintype "input"))
    )
    (net (code "42") (name "/US_TRIG_3V3") (class "Default")
      (node (ref "J26") (pin "4") (pinfunction "4_4") (pintype "passive"))
      (node (ref "U23") (pin "2") (pinfunction "2_2") (pintype "passive"))
    )
    (net (code "43") (name "/US_TRIG_5V") (class "Default")
      (node (ref "U21") (pin "3") (pinfunction "D_3") (pintype "bidirectional"))
      (node (ref "U23") (pin "4") (pinfunction "4_4") (pintype "passive"))
    )
    (net (code "44") (name "GND") (class "Default")
      (node (ref "C11") (pin "1") (pinfunction "1_1") (pintype "passive"))
      (node (ref "C12") (pin "1") (pinfunction "1_1") (pintype "passive"))
      (node (ref "C13") (pin "1") (pinfunction "1_1") (pintype "passive"))
      (node (ref "C21") (pin "1") (pinfunction "1_1") (pintype "passive"))
      (node (ref "C22") (pin "1") (pinfunction "1_1") (pintype "passive"))
      (node (ref "C512") (pin "1") (pinfunction "1_1") (pintype "passive"))
      (node (ref "C53") (pin "1") (pinfunction "1_1") (pintype "passive"))
      (node (ref "C56") (pin "1") (pinfunction "1_1") (pintype "passive"))
      (node (ref "C59") (pin "1") (pinfunction "1_1") (pintype "passive"))
      (node (ref "J01") (pin "2") (pinfunction "2_2") (pintype "passive"))
      (node (ref "J01") (pin "3") (pinfunction "3_3") (pintype "passive"))
      (node (ref "J11") (pin "10") (pinfunction "10_10") (pintype "passive"))
      (node (ref "J11") (pin "12") (pinfunction "12_12") (pintype "passive"))
      (node (ref "J11") (pin "13") (pinfunction "13_13") (pintype "passive"))
      (node (ref "J11") (pin "15") (pinfunction "15_15") (pintype "passive"))
      (node (ref "J11") (pin "18") (pinfunction "18_18") (pintype "passive"))
      (node (ref "J11") (pin "20") (pinfunction "20_20") (pintype "passive"))
      (node (ref "J11") (pin "5") (pinfunction "5_5") (pintype "passive"))
      (node (ref "J11") (pin "7") (pinfunction "7_7") (pintype "passive"))
      (node (ref "J12") (pin "1") (pinfunction "1_1") (pintype "passive"))
      (node (ref "J12") (pin "10") (pinfunction "10_10") (pintype "passive"))
      (node (ref "J12") (pin "11") (pinfunction "11_11") (pintype "passive"))
      (node (ref "J12") (pin "12") (pinfunction "12_12") (pintype "passive"))
      (node (ref "J12") (pin "13") (pinfunction "13_13") (pintype "passive"))
      (node (ref "J12") (pin "15") (pinfunction "15_15") (pintype "passive"))
      (node (ref "J12") (pin "20") (pinfunction "20_20") (pintype "passive"))
      (node (ref "J12") (pin "3") (pinfunction "3_3") (pintype "passive"))
      (node (ref "J12") (pin "8") (pinfunction "8_8") (pintype "passive"))
      (node (ref "J13") (pin "2") (pinfunction "2_2") (pintype "passive"))
      (node (ref "J13") (pin "6") (pinfunction "6_6") (pintype "passive"))
      (node (ref "J14") (pin "11") (pinfunction "11_11") (pintype "passive"))
      (node (ref "J14") (pin "5") (pinfunction "5_5") (pintype "passive"))
      (node (ref "J21") (pin "4") (pinfunction "4_4") (pintype "passive"))
      (node (ref "J22") (pin "4") (pinfunction "4_4") (pintype "passive"))
      (node (ref "J23") (pin "4") (pinfunction "4_4") (pintype "passive"))
      (node (ref "J24") (pin "4") (pinfunction "4_4") (pintype "passive"))
      (node (ref "J25") (pin "4") (pinfunction "4_4") (pintype "passive"))
      (node (ref "J26") (pin "11") (pinfunction "11_11") (pintype "passive"))
      (node (ref "J26") (pin "5") (pinfunction "5_5") (pintype "passive"))
      (node (ref "J31") (pin "2") (pinfunction "2_2") (pintype "passive"))
      (node (ref "J31") (pin "6") (pinfunction "6_6") (pintype "passive"))
      (node (ref "J32") (pin "1") (pinfunction "1_1") (pintype "passive"))
      (node (ref "J33") (pin "2") (pinfunction "2_2") (pintype "passive"))
      (node (ref "J34") (pin "11") (pinfunction "11_11") (pintype "passive"))
      (node (ref "J34") (pin "5") (pinfunction "5_5") (pintype "passive"))
      (node (ref "Q41") (pin "2") (pinfunction "2_2") (pintype "passive"))
      (node (ref "Q42") (pin "2") (pinfunction "2_2") (pintype "passive"))
      (node (ref "Q43") (pin "2") (pinfunction "2_2") (pintype "passive"))
      (node (ref "Q44") (pin "2") (pinfunction "2_2") (pintype "passive"))
      (node (ref "R34") (pin "1") (pinfunction "1_1") (pintype "passive"))
      (node (ref "R36") (pin "2") (pinfunction "2_2") (pintype "passive"))
      (node (ref "R513") (pin "1") (pinfunction "1_1") (pintype "passive"))
      (node (ref "R514") (pin "1") (pinfunction "1_1") (pintype "passive"))
      (node (ref "R520") (pin "1") (pinfunction "1_1") (pintype "passive"))
      (node (ref "R521") (pin "1") (pinfunction "1_1") (pintype "passive"))
      (node (ref "R527") (pin "1") (pinfunction "1_1") (pintype "passive"))
      (node (ref "R528") (pin "1") (pinfunction "1_1") (pintype "passive"))
      (node (ref "R56") (pin "1") (pinfunction "1_1") (pintype "passive"))
      (node (ref "R57") (pin "1") (pinfunction "1_1") (pintype "passive"))
      (node (ref "U21") (pin "6") (pinfunction "~{EN}_6") (pintype "input"))
      (node (ref "U21") (pin "8") (pinfunction "GND_8") (pintype "power_in"))
      (node (ref "U22") (pin "6") (pinfunction "~{EN}_6") (pintype "input"))
      (node (ref "U22") (pin "8") (pinfunction "GND_8") (pintype "power_in"))
      (node (ref "U23") (pin "3") (pinfunction "GND_3") (pintype "passive"))
      (node (ref "U24") (pin "3") (pinfunction "GND_3") (pintype "passive"))
      (node (ref "U31") (pin "2") (pinfunction "VS-_2") (pintype "power_in"))
      (node (ref "U32") (pin "3") (pinfunction "GND_3") (pintype "passive"))
    )
    (net (code "45") (name "Net-(D1-Pad1)") (class "Default")
      (node (ref "D1") (pin "1") (pinfunction "1_1") (pintype "passive"))
      (node (ref "Q41") (pin "3") (pinfunction "3_3") (pintype "passive"))
    )
    (net (code "46") (name "Net-(D1-Pad2)") (class "Default")
      (node (ref "D1") (pin "2") (pinfunction "2_2") (pintype "passive"))
      (node (ref "R41") (pin "1") (pinfunction "1_1") (pintype "passive"))
    )
    (net (code "47") (name "Net-(D2-Pad1)") (class "Default")
      (node (ref "D2") (pin "1") (pinfunction "1_1") (pintype "passive"))
      (node (ref "Q42") (pin "3") (pinfunction "3_3") (pintype "passive"))
    )
    (net (code "48") (name "Net-(D2-Pad2)") (class "Default")
      (node (ref "D2") (pin "2") (pinfunction "2_2") (pintype "passive"))
      (node (ref "R42") (pin "1") (pinfunction "1_1") (pintype "passive"))
    )
    (net (code "49") (name "Net-(D3-Pad1)") (class "Default")
      (node (ref "D3") (pin "1") (pinfunction "1_1") (pintype "passive"))
      (node (ref "Q43") (pin "3") (pinfunction "3_3") (pintype "passive"))
    )
    (net (code "50") (name "Net-(D3-Pad2)") (class "Default")
      (node (ref "D3") (pin "2") (pinfunction "2_2") (pintype "passive"))
      (node (ref "R43") (pin "1") (pinfunction "1_1") (pintype "passive"))
    )
    (net (code "51") (name "Net-(D4-Pad1)") (class "Default")
      (node (ref "D4") (pin "1") (pinfunction "1_1") (pintype "passive"))
      (node (ref "Q44") (pin "3") (pinfunction "3_3") (pintype "passive"))
    )
    (net (code "52") (name "Net-(D4-Pad2)") (class "Default")
      (node (ref "D4") (pin "2") (pinfunction "2_2") (pintype "passive"))
      (node (ref "R44") (pin "1") (pinfunction "1_1") (pintype "passive"))
    )
    (net (code "53") (name "Net-(Q51A-B)") (class "Default")
      (node (ref "C53") (pin "2") (pinfunction "2_2") (pintype "passive"))
      (node (ref "Q51") (pin "2") (pinfunction "B_2") (pintype "passive"))
      (node (ref "R55") (pin "2") (pinfunction "2_2") (pintype "passive"))
      (node (ref "R56") (pin "2") (pinfunction "2_2") (pintype "passive"))
    )
    (net (code "54") (name "Net-(Q51A-C)") (class "Default")
      (node (ref "C51") (pin "1") (pinfunction "1_1") (pintype "passive"))
      (node (ref "C52") (pin "1") (pinfunction "1_1") (pintype "passive"))
      (node (ref "Q51") (pin "6") (pinfunction "C_6") (pintype "passive"))
      (node (ref "R51") (pin "1") (pinfunction "1_1") (pintype "passive"))
      (node (ref "R52") (pin "2") (pinfunction "2_2") (pintype "passive"))
    )
    (net (code "55") (name "Net-(Q51A-E)") (class "Default")
      (node (ref "Q51") (pin "1") (pinfunction "E_1") (pintype "passive"))
      (node (ref "R57") (pin "2") (pinfunction "2_2") (pintype "passive"))
    )
    (net (code "56") (name "Net-(Q51B-B)") (class "Default")
      (node (ref "C59") (pin "2") (pinfunction "2_2") (pintype "passive"))
      (node (ref "Q51") (pin "5") (pinfunction "B_5") (pintype "passive"))
      (node (ref "R519") (pin "2") (pinfunction "2_2") (pintype "passive"))
      (node (ref "R520") (pin "2") (pinfunction "2_2") (pintype "passive"))
    )
    (net (code "57") (name "Net-(Q51B-C)") (class "Default")
      (node (ref "C57") (pin "1") (pinfunction "1_1") (pintype "passive"))
      (node (ref "C58") (pin "1") (pinfunction "1_1") (pintype "passive"))
      (node (ref "Q51") (pin "3") (pinfunction "C_3") (pintype "passive"))
      (node (ref "R515") (pin "1") (pinfunction "1_1") (pintype "passive"))
      (node (ref "R516") (pin "2") (pinfunction "2_2") (pintype "passive"))
    )
    (net (code "58") (name "Net-(Q51B-E)") (class "Default")
      (node (ref "Q51") (pin "4") (pinfunction "E_4") (pintype "passive"))
      (node (ref "R521") (pin "2") (pinfunction "2_2") (pintype "passive"))
    )
    (net (code "59") (name "Net-(Q52A-B)") (class "Default")
      (node (ref "C56") (pin "2") (pinfunction "2_2") (pintype "passive"))
      (node (ref "Q52") (pin "2") (pinfunction "B_2") (pintype "passive"))
      (node (ref "R512") (pin "2") (pinfunction "2_2") (pintype "passive"))
      (node (ref "R513") (pin "2") (pinfunction "2_2") (pintype "passive"))
    )
    (net (code "60") (name "Net-(Q52A-C)") (class "Default")
      (node (ref "C54") (pin "1") (pinfunction "1_1") (pintype "passive"))
      (node (ref "C55") (pin "1") (pinfunction "1_1") (pintype "passive"))
      (node (ref "Q52") (pin "6") (pinfunction "C_6") (pintype "passive"))
      (node (ref "R58") (pin "1") (pinfunction "1_1") (pintype "passive"))
      (node (ref "R59") (pin "2") (pinfunction "2_2") (pintype "passive"))
    )
    (net (code "61") (name "Net-(Q52A-E)") (class "Default")
      (node (ref "Q52") (pin "1") (pinfunction "E_1") (pintype "passive"))
      (node (ref "R514") (pin "2") (pinfunction "2_2") (pintype "passive"))
    )
    (net (code "62") (name "Net-(Q52B-B)") (class "Default")
      (node (ref "C512") (pin "2") (pinfunction "2_2") (pintype "passive"))
      (node (ref "Q52") (pin "5") (pinfunction "B_5") (pintype "passive"))
      (node (ref "R526") (pin "2") (pinfunction "2_2") (pintype "passive"))
      (node (ref "R527") (pin "2") (pinfunction "2_2") (pintype "passive"))
    )
    (net (code "63") (name "Net-(Q52B-C)") (class "Default")
      (node (ref "C510") (pin "1") (pinfunction "1_1") (pintype "passive"))
      (node (ref "C511") (pin "1") (pinfunction "1_1") (pintype "passive"))
      (node (ref "Q52") (pin "3") (pinfunction "C_3") (pintype "passive"))
      (node (ref "R522") (pin "1") (pinfunction "1_1") (pintype "passive"))
      (node (ref "R523") (pin "2") (pinfunction "2_2") (pintype "passive"))
    )
    (net (code "64") (name "Net-(Q52B-E)") (class "Default")
      (node (ref "Q52") (pin "4") (pinfunction "E_4") (pintype "passive"))
      (node (ref "R528") (pin "2") (pinfunction "2_2") (pintype "passive"))
    )
    (net (code "65") (name "Net-(Q53-Pad1)") (class "Default")
      (node (ref "Q53") (pin "1") (pinfunction "1_1") (pintype "passive"))
      (node (ref "R51") (pin "2") (pinfunction "2_2") (pintype "passive"))
    )
    (net (code "66") (name "Net-(Q54-Pad1)") (class "Default")
      (node (ref "Q54") (pin "1") (pinfunction "1_1") (pintype "passive"))
      (node (ref "R58") (pin "2") (pinfunction "2_2") (pintype "passive"))
    )
    (net (code "67") (name "Net-(Q55-Pad1)") (class "Default")
      (node (ref "Q55") (pin "1") (pinfunction "1_1") (pintype "passive"))
      (node (ref "R515") (pin "2") (pinfunction "2_2") (pintype "passive"))
    )
    (net (code "68") (name "Net-(Q56-Pad1)") (class "Default")
      (node (ref "Q56") (pin "1") (pinfunction "1_1") (pintype "passive"))
      (node (ref "R522") (pin "2") (pinfunction "2_2") (pintype "passive"))
    )
    (net (code "69") (name "Net-(R33-Pad1)") (class "Default")
      (node (ref "R33") (pin "1") (pinfunction "1_1") (pintype "passive"))
      (node (ref "R35") (pin "2") (pinfunction "2_2") (pintype "passive"))
    )
    (net (code "70") (name "Net-(R53-Pad1)") (class "Default")
      (node (ref "R53") (pin "1") (pinfunction "1_1") (pintype "passive"))
      (node (ref "R54") (pin "2") (pinfunction "2_2") (pintype "passive"))
      (node (ref "R55") (pin "1") (pinfunction "1_1") (pintype "passive"))
    )
    (net (code "71") (name "Net-(R510-Pad1)") (class "Default")
      (node (ref "R510") (pin "1") (pinfunction "1_1") (pintype "passive"))
      (node (ref "R511") (pin "2") (pinfunction "2_2") (pintype "passive"))
      (node (ref "R512") (pin "1") (pinfunction "1_1") (pintype "passive"))
    )
    (net (code "72") (name "Net-(R517-Pad1)") (class "Default")
      (node (ref "R517") (pin "1") (pinfunction "1_1") (pintype "passive"))
      (node (ref "R518") (pin "2") (pinfunction "2_2") (pintype "passive"))
      (node (ref "R519") (pin "1") (pinfunction "1_1") (pintype "passive"))
    )
    (net (code "73") (name "Net-(R524-Pad1)") (class "Default")
      (node (ref "R524") (pin "1") (pinfunction "1_1") (pintype "passive"))
      (node (ref "R525") (pin "2") (pinfunction "2_2") (pintype "passive"))
      (node (ref "R526") (pin "1") (pinfunction "1_1") (pintype "passive"))
    )
    (net (code "74") (name "Net-(U31-IN+)") (class "Default")
      (node (ref "R31") (pin "2") (pinfunction "2_2") (pintype "passive"))
      (node (ref "R32") (pin "1") (pinfunction "1_1") (pintype "passive"))
      (node (ref "U31") (pin "3") (pinfunction "IN+_3") (pintype "tri_state"))
    )
    (net (code "75") (name "Net-(U31-IN-)") (class "Default")
      (node (ref "R34") (pin "2") (pinfunction "2_2") (pintype "passive"))
      (node (ref "R35") (pin "1") (pinfunction "1_1") (pintype "passive"))
      (node (ref "R35") (pin "3") (pinfunction "3_3") (pintype "passive"))
      (node (ref "U31") (pin "4") (pinfunction "IN-_4") (pintype "tri_state"))
    )
    (net (code "76") (name "Net-(U31-OUT)") (class "Default")
      (node (ref "R32") (pin "2") (pinfunction "2_2") (pintype "passive"))
      (node (ref "R36") (pin "1") (pinfunction "1_1") (pintype "passive"))
      (node (ref "U31") (pin "1") (pinfunction "OUT_1") (pintype "passive"))
      (node (ref "U32") (pin "2") (pinfunction "2_2") (pintype "passive"))
    )
    (net (code "77") (name "unconnected-(J11-Pad2)") (class "Default")
      (node (ref "J11") (pin "2") (pinfunction "2_2") (pintype "passive+no_connect"))
    )
    (net (code "78") (name "unconnected-(J11-Pad4)") (class "Default")
      (node (ref "J11") (pin "4") (pinfunction "4_4") (pintype "passive+no_connect"))
    )
    (net (code "79") (name "unconnected-(J11-Pad6)") (class "Default")
      (node (ref "J11") (pin "6") (pinfunction "6_6") (pintype "passive+no_connect"))
    )
    (net (code "80") (name "unconnected-(J11-Pad8)") (class "Default")
      (node (ref "J11") (pin "8") (pinfunction "8_8") (pintype "passive+no_connect"))
    )
    (net (code "81") (name "unconnected-(J11-Pad9)") (class "Default")
      (node (ref "J11") (pin "9") (pinfunction "9_9") (pintype "passive+no_connect"))
    )
    (net (code "82") (name "unconnected-(J11-Pad11)") (class "Default")
      (node (ref "J11") (pin "11") (pinfunction "11_11") (pintype "passive+no_connect"))
    )
    (net (code "83") (name "unconnected-(J11-Pad17)") (class "Default")
      (node (ref "J11") (pin "17") (pinfunction "17_17") (pintype "passive+no_connect"))
    )
    (net (code "84") (name "unconnected-(J11-Pad19)") (class "Default")
      (node (ref "J11") (pin "19") (pinfunction "19_19") (pintype "passive+no_connect"))
    )
    (net (code "85") (name "unconnected-(J14-Pad6)") (class "Default")
      (node (ref "J14") (pin "6") (pinfunction "6_6") (pintype "passive+no_connect"))
    )
    (net (code "86") (name "unconnected-(J14-Pad8)") (class "Default")
      (node (ref "J14") (pin "8") (pinfunction "8_8") (pintype "passive+no_connect"))
    )
    (net (code "87") (name "unconnected-(J14-Pad12)") (class "Default")
      (node (ref "J14") (pin "12") (pinfunction "12_12") (pintype "passive+no_connect"))
    )
    (net (code "88") (name "unconnected-(J26-Pad6)") (class "Default")
      (node (ref "J26") (pin "6") (pinfunction "6_6") (pintype "passive+no_connect"))
    )
    (net (code "89") (name "unconnected-(J26-Pad12)") (class "Default")
      (node (ref "J26") (pin "12") (pinfunction "12_12") (pintype "passive+no_connect"))
    )
    (net (code "90") (name "unconnected-(J34-Pad6)") (class "Default")
      (node (ref "J34") (pin "6") (pinfunction "6_6") (pintype "passive+no_connect"))
    )
    (net (code "91") (name "unconnected-(J34-Pad10)") (class "Default")
      (node (ref "J34") (pin "10") (pinfunction "10_10") (pintype "passive+no_connect"))
    )
    (net (code "92") (name "unconnected-(J34-Pad12)") (class "Default")
      (node (ref "J34") (pin "12") (pinfunction "12_12") (pintype "passive+no_connect"))
    )
    (net (code "93") (name "unconnected-(U21-NC-Pad7)") (class "Default")
      (node (ref "U21") (pin "7") (pinfunction "NC_7") (pintype "power_in+no_connect"))
    )
    (net (code "94") (name "unconnected-(U21-S5-Pad5)") (class "Default")
      (node (ref "U21") (pin "5") (pinfunction "S5_5") (pintype "bidirectional+no_connect"))
    )
    (net (code "95") (name "unconnected-(U21-S6-Pad2)") (class "Default")
      (node (ref "U21") (pin "2") (pinfunction "S6_2") (pintype "bidirectional+no_connect"))
    )
    (net (code "96") (name "unconnected-(U21-S7-Pad4)") (class "Default")
      (node (ref "U21") (pin "4") (pinfunction "S7_4") (pintype "bidirectional+no_connect"))
    )
    (net (code "97") (name "unconnected-(U22-NC-Pad7)") (class "Default")
      (node (ref "U22") (pin "7") (pinfunction "NC_7") (pintype "power_in+no_connect"))
    )
    (net (code "98") (name "unconnected-(U22-S5-Pad5)") (class "Default")
      (node (ref "U22") (pin "5") (pinfunction "S5_5") (pintype "bidirectional+no_connect"))
    )
    (net (code "99") (name "unconnected-(U22-S6-Pad2)") (class "Default")
      (node (ref "U22") (pin "2") (pinfunction "S6_2") (pintype "bidirectional+no_connect"))
    )
    (net (code "100") (name "unconnected-(U22-S7-Pad4)") (class "Default")
      (node (ref "U22") (pin "4") (pinfunction "S7_4") (pintype "bidirectional+no_connect"))
    )
    (net (code "101") (name "unconnected-(U23-NC-Pad1)") (class "Default")
      (node (ref "U23") (pin "1") (pinfunction "NC_1") (pintype "passive+no_connect"))
    )
    (net (code "102") (name "unconnected-(U24-NC-Pad1)") (class "Default")
      (node (ref "U24") (pin "1") (pinfunction "NC_1") (pintype "passive+no_connect"))
    )
    (net (code "103") (name "unconnected-(U32-NC-Pad1)") (class "Default")
      (node (ref "U32") (pin "1") (pinfunction "NC_1") (pintype "passive+no_connect"))
    )
  )
)
